# Conectores.net
KiCad netlist of a schematic drawn in Altium Designer
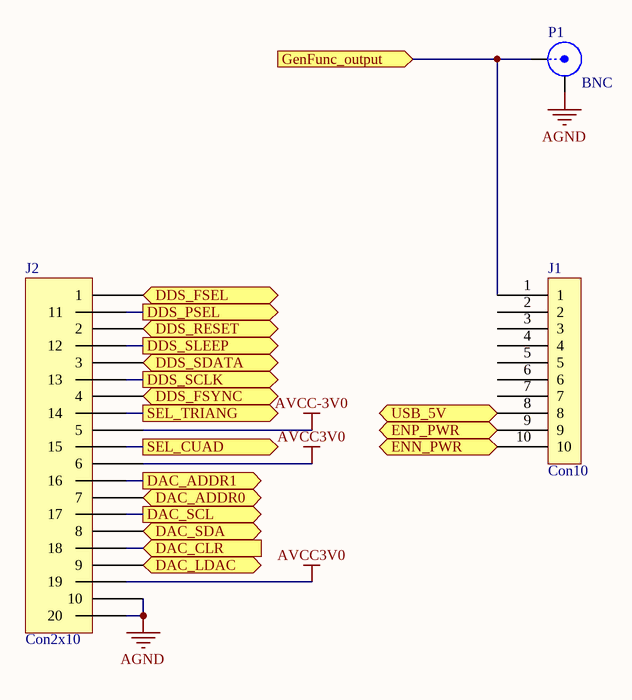
[diagram p0: Conectores.SchDoc]

(export (version "E")
  (design (tool "Eeschema 10.0.6"))
  (components
    (comp (ref "J1")
      (value "Con10")
      (footprint "Connector .1 x10")
      (description "Connector x10")
      (libsource (lib "Gen_func") (part "Con10"))
    )
    (comp (ref "J2")
      (value "Con2x10")
      (footprint "Con2x10")
      (description "Connector 2x10")
      (libsource (lib "Gen_func") (part "Con2x10"))
    )
    (comp (ref "P1")
      (value "BNC")
      (footprint "BNC")
      (description "BNC Elbow Connector")
      (fields (field (name "PUBLISHER") "Altium Limited"))
      (libsource (lib "Gen_func") (part "BNC"))
    )
  )
  (nets
    (net (code "1") (name "/DAC_ADDR0") (class "Default")
      (node (ref "J2") (pin "7") (pinfunction "7_7") (pintype "passive"))
    )
    (net (code "2") (name "/DAC_ADDR1") (class "Default")
      (node (ref "J2") (pin "16") (pinfunction "16_16") (pintype "passive"))
    )
    (net (code "3") (name "/DAC_CLR") (class "Default")
      (node (ref "J2") (pin "18") (pinfunction "18_18") (pintype "passive"))
    )
    (net (code "4") (name "/DAC_LDAC") (class "Default")
      (node (ref "J2") (pin "9") (pinfunction "9_9") (pintype "passive"))
    )
    (net (code "5") (name "/DAC_SCL") (class "Default")
      (node (ref "J2") (pin "17") (pinfunction "17_17") (pintype "passive"))
    )
    (net (code "6") (name "/DAC_SDA") (class "Default")
      (node (ref "J2") (pin "8") (pinfunction "8_8") (pintype "passive"))
    )
    (net (code "7") (name "/DDS_FSEL") (class "Default")
      (node (ref "J2") (pin "1") (pinfunction "1_1") (pintype "passive"))
    )
    (net (code "8") (name "/DDS_FSYNC") (class "Default")
      (node (ref "J2") (pin "4") (pinfunction "4_4") (pintype "passive"))
    )
    (net (code "9") (name "/DDS_PSEL") (class "Default")
      (node (ref "J2") (pin "11") (pinfunction "11_11") (pintype "passive"))
    )
    (net (code "10") (name "/DDS_RESET") (class "Default")
      (node (ref "J2") (pin "2") (pinfunction "2_2") (pintype "passive"))
    )
    (net (code "11") (name "/DDS_SCLK") (class "Default")
      (node (ref "J2") (pin "13") (pinfunction "13_13") (pintype "passive"))
    )
    (net (code "12") (name "/DDS_SDATA") (class "Default")
      (node (ref "J2") (pin "3") (pinfunction "3_3") (pintype "passive"))
    )
    (net (code "13") (name "/DDS_SLEEP") (class "Default")
      (node (ref "J2") (pin "12") (pinfunction "12_12") (pintype "passive"))
    )
    (net (code "14") (name "/ENN_PWR") (class "Default")
      (node (ref "J1") (pin "10") (pinfunction "10_10") (pintype "passive"))
    )
    (net (code "15") (name "/ENP_PWR") (class "Default")
      (node (ref "J1") (pin "9") (pinfunction "9_9") (pintype "passive"))
    )
    (net (code "16") (name "/GenFunc_output") (class "Default")
      (node (ref "J1") (pin "1") (pinfunction "1_1") (pintype "passive"))
      (node (ref "P1") (pin "1") (pinfunction "X_1") (pintype "passive"))
    )
    (net (code "17") (name "/SEL_CUAD") (class "Default")
      (node (ref "J2") (pin "15") (pinfunction "15_15") (pintype "passive"))
    )
    (net (code "18") (name "/SEL_TRIANG") (class "Default")
      (node (ref "J2") (pin "14") (pinfunction "14_14") (pintype "passive"))
    )
    (net (code "19") (name "/USB_5V") (class "Default")
      (node (ref "J1") (pin "8") (pinfunction "8_8") (pintype "passive"))
    )
    (net (code "20") (name "AGND") (class "Default")
      (node (ref "J2") (pin "10") (pinfunction "10_10") (pintype "passive"))
      (node (ref "J2") (pin "20") (pinfunction "20_20") (pintype "passive"))
      (node (ref "P1") (pin "2") (pinfunction "Y_2") (pintype "passive"))
    )
    (net (code "21") (name "AVCC-3V0") (class "Default")
      (node (ref "J2") (pin "5") (pinfunction "5_5") (pintype "passive"))
    )
    (net (code "22") (name "AVCC3V0") (class "Default")
      (node (ref "J2") (pin "19") (pinfunction "19_19") (pintype "passive"))
      (node (ref "J2") (pin "6") (pinfunction "6_6") (pintype "passive"))
    )
    (net (code "23") (name "unconnected-(J1-Pad2)") (class "Default")
      (node (ref "J1") (pin "2") (pinfunction "2_2") (pintype "passive"))
    )
    (net (code "24") (name "unconnected-(J1-Pad3)") (class "Default")
      (node (ref "J1") (pin "3") (pinfunction "3_3") (pintype "passive"))
    )
    (net (code "25") (name "unconnected-(J1-Pad4)") (class "Default")
      (node (ref "J1") (pin "4") (pinfunction "4_4") (pintype "passive"))
    )
    (net (code "26") (name "unconnected-(J1-Pad5)") (class "Default")
      (node (ref "J1") (pin "5") (pinfunction "5_5") (pintype "passive"))
    )
    (net (code "27") (name "unconnected-(J1-Pad6)") (class "Default")
      (node (ref "J1") (pin "6") (pinfunction "6_6") (pintype "passive"))
    )
    (net (code "28") (name "unconnected-(J1-Pad7)") (class "Default")
      (node (ref "J1") (pin "7") (pinfunction "7_7") (pintype "passive"))
    )
  )
)
